# shige7seg_breakout.net
KiCad netlist of a schematic drawn in EAGLE
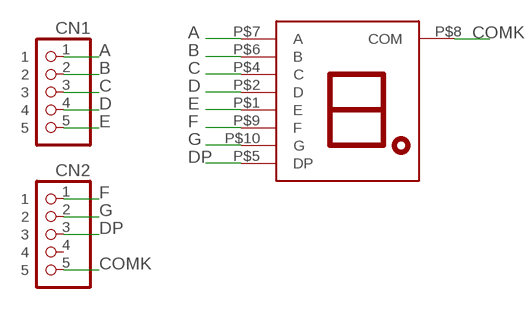
[diagram p0: schematic, sheet 1]

(export (version "E")
  (design (tool "Eeschema 10.0.6"))
  (components
    (comp (ref "CN1")
      (value "CON_PINHD-1X5")
      (footprint "eagle-import:1X05R")
      (libsource (lib "eagle-import") (part "CON_PINHD-1X5"))
    )
    (comp (ref "CN2")
      (value "CON_PINHD-1X5")
      (footprint "eagle-import:1X05R")
      (libsource (lib "eagle-import") (part "CON_PINHD-1X5"))
    )
    (comp (ref "D1")
      (value "LED_7SEG")
      (footprint "eagle-import:7SEG_10X7SMD")
      (libsource (lib "eagle-import") (part "LED_7SEG"))
    )
  )
  (nets
    (net (code "1") (name "/A") (class "Default")
      (node (ref "CN1") (pin "1") (pinfunction "1_1") (pintype "passive"))
      (node (ref "D1") (pin "P$7") (pinfunction "A_P$7") (pintype "bidirectional"))
    )
    (net (code "2") (name "/B") (class "Default")
      (node (ref "CN1") (pin "2") (pinfunction "2_2") (pintype "passive"))
      (node (ref "D1") (pin "P$6") (pinfunction "B_P$6") (pintype "bidirectional"))
    )
    (net (code "3") (name "/C") (class "Default")
      (node (ref "CN1") (pin "3") (pinfunction "3_3") (pintype "passive"))
      (node (ref "D1") (pin "P$4") (pinfunction "C_P$4") (pintype "bidirectional"))
    )
    (net (code "4") (name "/COMK") (class "Default")
      (node (ref "CN2") (pin "5") (pinfunction "5_5") (pintype "passive"))
      (node (ref "D1") (pin "P$8") (pinfunction "COM_P$8") (pintype "bidirectional"))
    )
    (net (code "5") (name "/D") (class "Default")
      (node (ref "CN1") (pin "4") (pinfunction "4_4") (pintype "passive"))
      (node (ref "D1") (pin "P$2") (pinfunction "D_P$2") (pintype "bidirectional"))
    )
    (net (code "6") (name "/DP") (class "Default")
      (node (ref "CN2") (pin "3") (pinfunction "3_3") (pintype "passive"))
      (node (ref "D1") (pin "P$5") (pinfunction "DP_P$5") (pintype "bidirectional"))
    )
    (net (code "7") (name "/E") (class "Default")
      (node (ref "CN1") (pin "5") (pinfunction "5_5") (pintype "passive"))
      (node (ref "D1") (pin "P$1") (pinfunction "E_P$1") (pintype "bidirectional"))
    )
    (net (code "8") (name "/F") (class "Default")
      (node (ref "CN2") (pin "1") (pinfunction "1_1") (pintype "passive"))
      (node (ref "D1") (pin "P$9") (pinfunction "F_P$9") (pintype "bidirectional"))
    )
    (net (code "9") (name "/G") (class "Default")
      (node (ref "CN2") (pin "2") (pinfunction "2_2") (pintype "passive"))
      (node (ref "D1") (pin "P$10") (pinfunction "G_P$10") (pintype "bidirectional"))
    )
    (net (code "10") (name "unconnected-(CN2-Pad4)") (class "Default")
      (node (ref "CN2") (pin "4") (pinfunction "4_4") (pintype "passive"))
    )
  )
)
